# cSLIM_GPS.net
KiCad netlist of a schematic drawn in Altium Designer
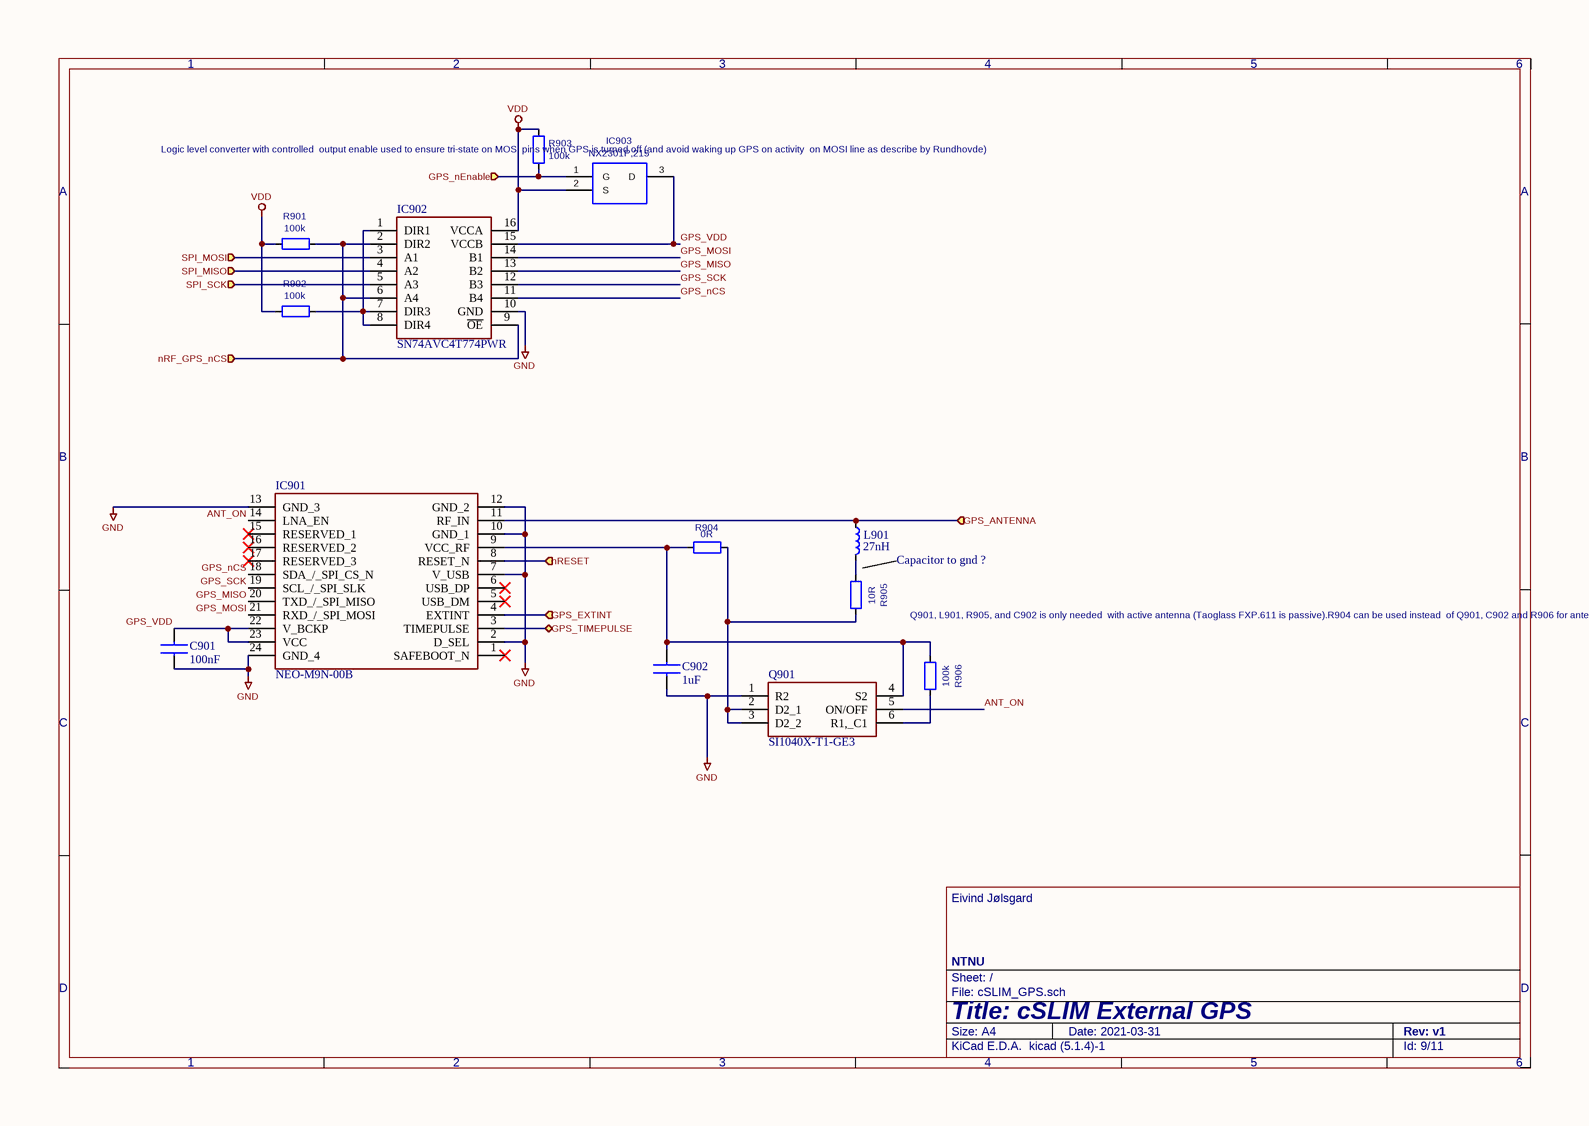
[diagram p0: cSLIM_GPS.SchDoc]

(export (version "E")
  (design (tool "Eeschema 10.0.6"))
  (components
    (comp (ref "C901")
      (value "100nF")
      (footprint "cSLIM-SA:CAPC1608X90N")
      (description "Capacitor")
      (fields
        (field (name "MANUFACTURER_PART_NUMBER") "06033G104ZAT2A")
        (field (name "MOUSER PART NUMBER") "581-06033G104Z")
      )
      (libsource (lib "cSLIM-SA") (part "C"))
    )
    (comp (ref "C902")
      (value "1uF")
      (footprint "cSLIM-SA:CAPC1608X90N")
      (description "Capacitor")
      (fields
        (field (name "MANUFACTURER_PART_NUMBER") "06033G104ZAT2A")
        (field (name "MOUSER PART NUMBER") "581-06033G104Z")
      )
      (libsource (lib "cSLIM-SA") (part "C"))
    )
    (comp (ref "IC901")
      (value "NEO-M9N-00B")
      (footprint "cSLIM-SA:NEOM9N00B")
      (description "Integrated Circuit")
      (fields (field (name "MOUSER PART NUMBER") "377-NEO-M9N-00B"))
      (libsource (lib "cSLIM-SA") (part "NEO-M9N-00B"))
    )
    (comp (ref "IC902")
      (value "SN74AVC4T774PWR")
      (footprint "cSLIM-SA:SOP65P640X120-16N")
      (description "Integrated Circuit")
      (fields (field (name "MOUSER PART NUMBER") "595-SN74AVC4T774PWR"))
      (libsource (lib "cSLIM-SA") (part "SN74AVC4T774PWR"))
    )
    (comp (ref "IC903")
      (value "NX2301P,215")
      (footprint "SOT95P230X110-3N")
      (fields (field (name "MOUSER PART NUMBER") "771-NX2301P215"))
      (libsource (lib "SamacSys") (part "NX2301P,215"))
    )
    (comp (ref "L901") (value "27nH") (footprint "L-1608") (libsource (lib "cSLIM-SA") (part "L")))
    (comp (ref "Q901")
      (value "SI1040X-T1-GE3")
      (footprint "cSLIM-SA:SOTFL50P160X60-6N")
      (description "MOSFET (N-Channel)")
      (fields (field (name "MOUSER PART NUMBER") "781-SI1040X-T1-GE3"))
      (libsource (lib "cSLIM-SA") (part "SI1040X-T1-GE3"))
    )
    (comp (ref "R901") (value "100k") (footprint "RESC1608X55N") (libsource (lib "") (part "R_1")))
    (comp (ref "R902") (value "100k") (footprint "RESC1608X55N") (libsource (lib "") (part "R_1")))
    (comp (ref "R903") (value "100k") (footprint "RESC1608X55N") (libsource (lib "cSLIM-SA") (part "R")))
    (comp (ref "R904") (value "0R") (footprint "RESC1608X55N") (libsource (lib "") (part "R_1")))
    (comp (ref "R905") (value "10R") (footprint "RESC1608X55N") (libsource (lib "cSLIM-SA") (part "R")))
    (comp (ref "R906") (value "100k") (footprint "RESC1608X55N") (libsource (lib "cSLIM-SA") (part "R")))
  )
  (nets
    (net (code "1") (name "/ANT_ON") (class "Default")
      (node (ref "IC901") (pin "14") (pinfunction "LNA_EN_14") (pintype "passive"))
      (node (ref "Q901") (pin "5") (pinfunction "ON/OFF_5") (pintype "passive"))
    )
    (net (code "2") (name "/GPS_ANTENNA") (class "Default")
      (node (ref "IC901") (pin "11") (pinfunction "RF_IN_11") (pintype "passive"))
      (node (ref "L901") (pin "1") (pinfunction "1_1") (pintype "passive"))
    )
    (net (code "3") (name "/GPS_EXTINT") (class "Default")
      (node (ref "IC901") (pin "4") (pinfunction "EXTINT_4") (pintype "passive"))
    )
    (net (code "4") (name "/GPS_MISO") (class "Default")
      (node (ref "IC901") (pin "20") (pinfunction "TXD_/_SPI_MISO_20") (pintype "passive"))
      (node (ref "IC902") (pin "13") (pinfunction "B2_13") (pintype "passive"))
    )
    (net (code "5") (name "/GPS_MOSI") (class "Default")
      (node (ref "IC901") (pin "21") (pinfunction "RXD_/_SPI_MOSI_21") (pintype "passive"))
      (node (ref "IC902") (pin "14") (pinfunction "B1_14") (pintype "passive"))
    )
    (net (code "6") (name "/GPS_SCK") (class "Default")
      (node (ref "IC901") (pin "19") (pinfunction "SCL_/_SPI_SLK_19") (pintype "passive"))
      (node (ref "IC902") (pin "12") (pinfunction "B3_12") (pintype "passive"))
    )
    (net (code "7") (name "/GPS_TIMEPULSE") (class "Default")
      (node (ref "IC901") (pin "3") (pinfunction "TIMEPULSE_3") (pintype "passive"))
    )
    (net (code "8") (name "/GPS_VDD") (class "Default")
      (node (ref "C901") (pin "1") (pinfunction "1_1") (pintype "passive"))
      (node (ref "IC901") (pin "22") (pinfunction "V_BCKP_22") (pintype "passive"))
      (node (ref "IC901") (pin "23") (pinfunction "VCC_23") (pintype "passive"))
      (node (ref "IC902") (pin "15") (pinfunction "VCCB_15") (pintype "passive"))
      (node (ref "IC903") (pin "3") (pinfunction "D_3") (pintype "passive"))
    )
    (net (code "9") (name "/GPS_nCS") (class "Default")
      (node (ref "IC901") (pin "18") (pinfunction "SDA_/_SPI_CS_N_18") (pintype "passive"))
      (node (ref "IC902") (pin "11") (pinfunction "B4_11") (pintype "passive"))
    )
    (net (code "10") (name "/GPS_nEnable") (class "Default")
      (node (ref "IC903") (pin "1") (pinfunction "G_1") (pintype "passive"))
      (node (ref "R903") (pin "1") (pinfunction "1_1") (pintype "passive"))
    )
    (net (code "11") (name "/SPI_MISO") (class "Default")
      (node (ref "IC902") (pin "4") (pinfunction "A2_4") (pintype "passive"))
    )
    (net (code "12") (name "/SPI_MOSI") (class "Default")
      (node (ref "IC902") (pin "3") (pinfunction "A1_3") (pintype "passive"))
    )
    (net (code "13") (name "/SPI_SCK") (class "Default")
      (node (ref "IC902") (pin "5") (pinfunction "A3_5") (pintype "passive"))
    )
    (net (code "14") (name "/nRESET") (class "Default")
      (node (ref "IC901") (pin "8") (pinfunction "RESET_N_8") (pintype "passive"))
    )
    (net (code "15") (name "/nRF_GPS_nCS") (class "Default")
      (node (ref "IC902") (pin "2") (pinfunction "DIR2_2") (pintype "passive"))
      (node (ref "IC902") (pin "6") (pinfunction "A4_6") (pintype "passive"))
      (node (ref "IC902") (pin "9") (pinfunction "~{OE}_9") (pintype "passive"))
      (node (ref "R901") (pin "1") (pinfunction "1_1") (pintype "passive"))
    )
    (net (code "16") (name "GND") (class "Default")
      (node (ref "C901") (pin "2") (pinfunction "2_2") (pintype "passive"))
      (node (ref "C902") (pin "2") (pinfunction "2_2") (pintype "passive"))
      (node (ref "IC901") (pin "10") (pinfunction "GND_1_10") (pintype "passive"))
      (node (ref "IC901") (pin "12") (pinfunction "GND_2_12") (pintype "passive"))
      (node (ref "IC901") (pin "13") (pinfunction "GND_3_13") (pintype "passive"))
      (node (ref "IC901") (pin "2") (pinfunction "D_SEL_2") (pintype "passive"))
      (node (ref "IC901") (pin "24") (pinfunction "GND_4_24") (pintype "passive"))
      (node (ref "IC901") (pin "7") (pinfunction "V_USB_7") (pintype "passive"))
      (node (ref "IC902") (pin "10") (pinfunction "GND_10") (pintype "passive"))
      (node (ref "Q901") (pin "1") (pinfunction "R2_1") (pintype "passive"))
    )
    (net (code "17") (name "Net-(IC901-VCC_RF)") (class "Default")
      (node (ref "C902") (pin "1") (pinfunction "1_1") (pintype "passive"))
      (node (ref "IC901") (pin "9") (pinfunction "VCC_RF_9") (pintype "passive"))
      (node (ref "Q901") (pin "4") (pinfunction "S2_4") (pintype "passive"))
      (node (ref "R904") (pin "2") (pinfunction "2_2") (pintype "passive"))
      (node (ref "R906") (pin "2") (pinfunction "2_2") (pintype "passive"))
    )
    (net (code "18") (name "Net-(IC902-DIR1)") (class "Default")
      (node (ref "IC902") (pin "1") (pinfunction "DIR1_1") (pintype "passive"))
      (node (ref "IC902") (pin "7") (pinfunction "DIR3_7") (pintype "passive"))
      (node (ref "IC902") (pin "8") (pinfunction "DIR4_8") (pintype "passive"))
      (node (ref "R902") (pin "1") (pinfunction "1_1") (pintype "passive"))
    )
    (net (code "19") (name "Net-(L901-Pad2)") (class "Default")
      (node (ref "L901") (pin "2") (pinfunction "2_2") (pintype "passive"))
      (node (ref "R905") (pin "2") (pinfunction "2_2") (pintype "passive"))
    )
    (net (code "20") (name "Net-(Q901-D2_1)") (class "Default")
      (node (ref "Q901") (pin "2") (pinfunction "D2_1_2") (pintype "passive"))
      (node (ref "Q901") (pin "3") (pinfunction "D2_2_3") (pintype "passive"))
      (node (ref "R904") (pin "1") (pinfunction "1_1") (pintype "passive"))
      (node (ref "R905") (pin "1") (pinfunction "1_1") (pintype "passive"))
    )
    (net (code "21") (name "Net-(Q901-R1,_C1)") (class "Default")
      (node (ref "Q901") (pin "6") (pinfunction "R1,_C1_6") (pintype "passive"))
      (node (ref "R906") (pin "1") (pinfunction "1_1") (pintype "passive"))
    )
    (net (code "22") (name "VDD") (class "Default")
      (node (ref "IC902") (pin "16") (pinfunction "VCCA_16") (pintype "passive"))
      (node (ref "IC903") (pin "2") (pinfunction "S_2") (pintype "passive"))
      (node (ref "R901") (pin "2") (pinfunction "2_2") (pintype "passive"))
      (node (ref "R902") (pin "2") (pinfunction "2_2") (pintype "passive"))
      (node (ref "R903") (pin "2") (pinfunction "2_2") (pintype "passive"))
    )
    (net (code "23") (name "unconnected-(IC901-RESERVED_1-Pad15)") (class "Default")
      (node (ref "IC901") (pin "15") (pinfunction "RESERVED_1_15") (pintype "passive+no_connect"))
    )
    (net (code "24") (name "unconnected-(IC901-RESERVED_2-Pad16)") (class "Default")
      (node (ref "IC901") (pin "16") (pinfunction "RESERVED_2_16") (pintype "passive+no_connect"))
    )
    (net (code "25") (name "unconnected-(IC901-RESERVED_3-Pad17)") (class "Default")
      (node (ref "IC901") (pin "17") (pinfunction "RESERVED_3_17") (pintype "passive+no_connect"))
    )
    (net (code "26") (name "unconnected-(IC901-SAFEBOOT_N-Pad1)") (class "Default")
      (node (ref "IC901") (pin "1") (pinfunction "SAFEBOOT_N_1") (pintype "passive+no_connect"))
    )
    (net (code "27") (name "unconnected-(IC901-USB_DM-Pad5)") (class "Default")
      (node (ref "IC901") (pin "5") (pinfunction "USB_DM_5") (pintype "passive+no_connect"))
    )
    (net (code "28") (name "unconnected-(IC901-USB_DP-Pad6)") (class "Default")
      (node (ref "IC901") (pin "6") (pinfunction "USB_DP_6") (pintype "passive+no_connect"))
    )
  )
)
